# NanoRS485-MySens-v010-both-connectors.net
KiCad netlist of a schematic drawn in EAGLE
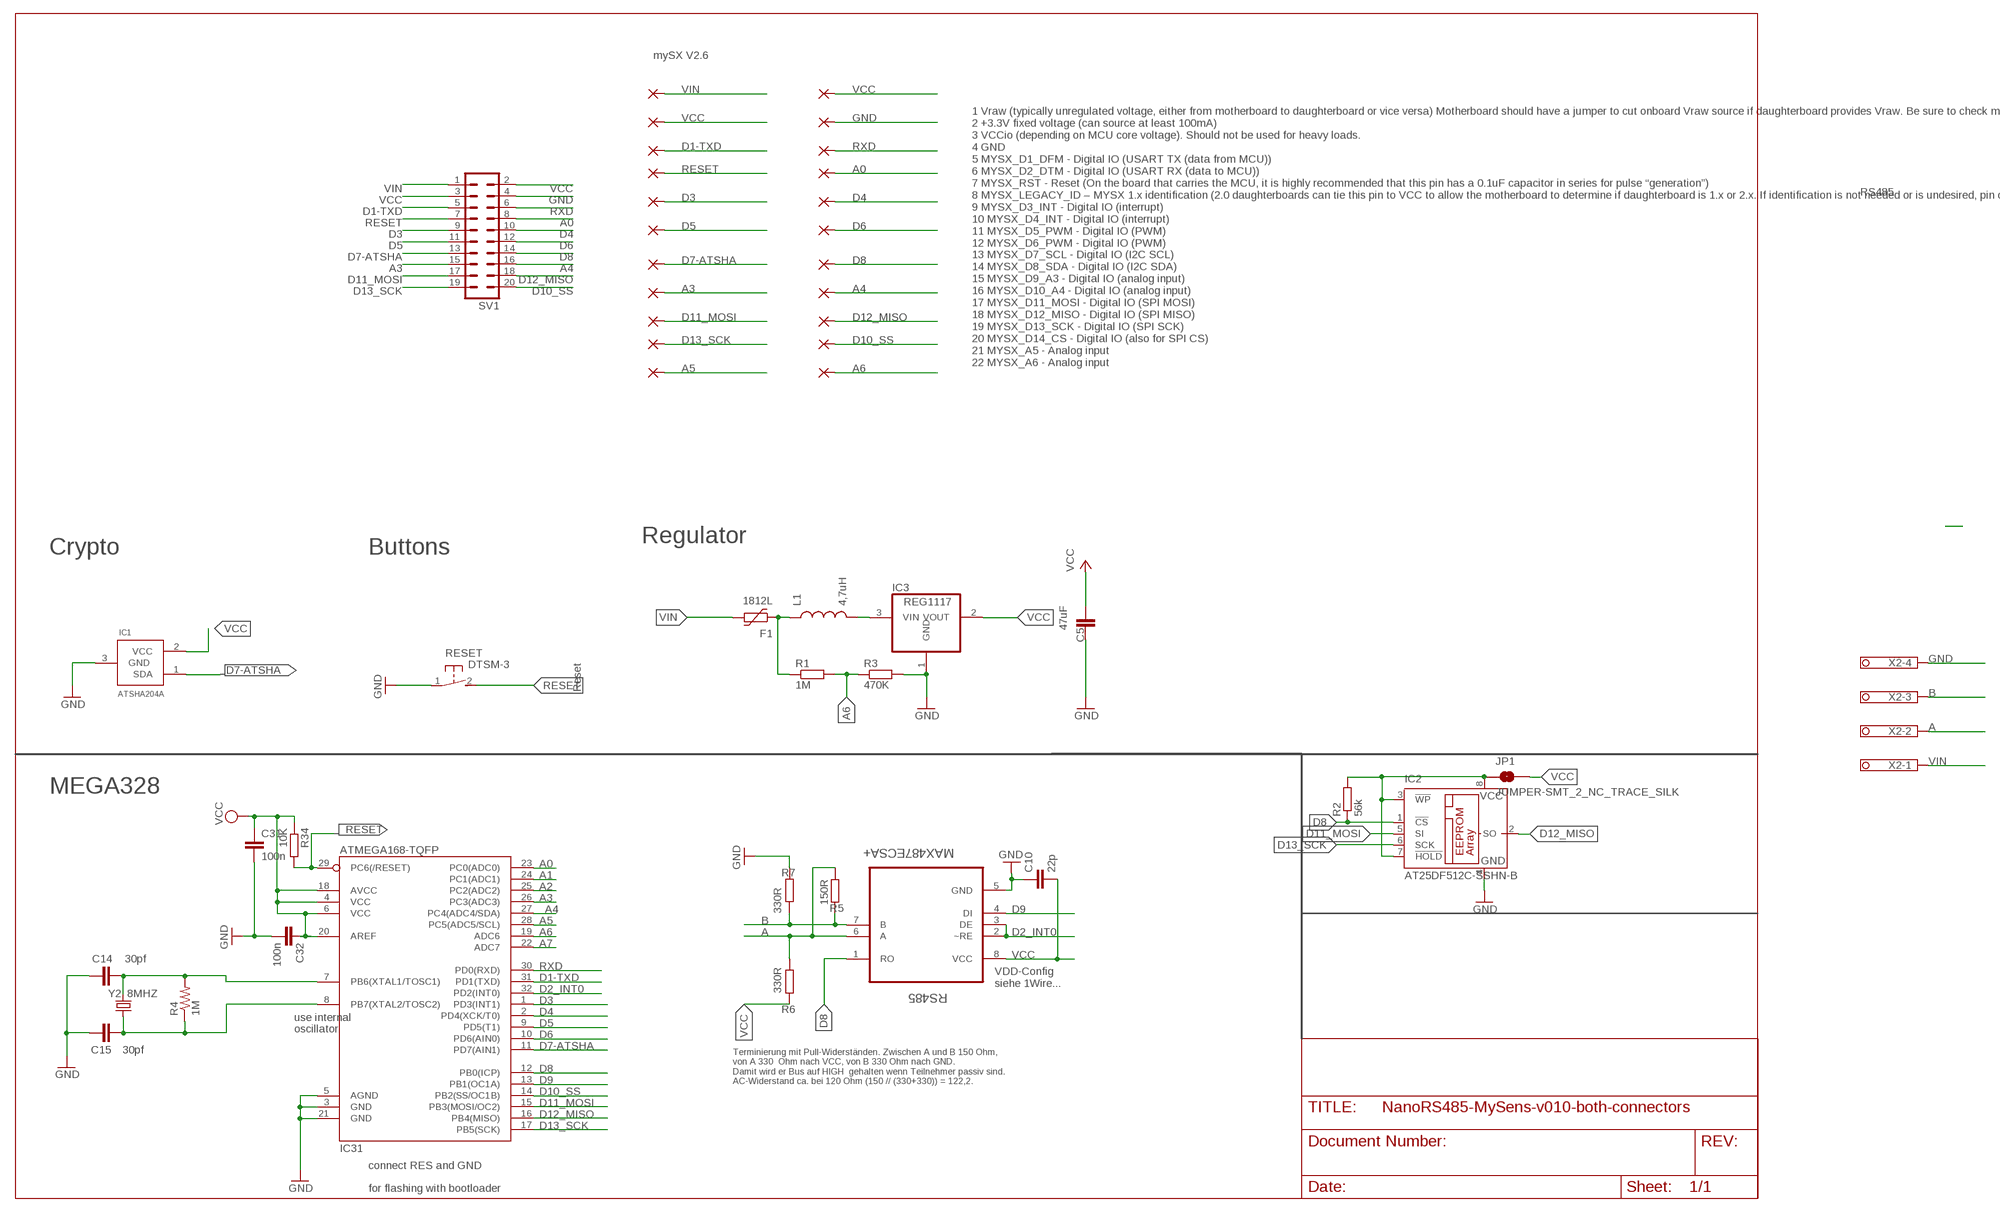
[diagram p0: schematic, sheet 1]

(export (version "E")
  (design (tool "Eeschema 10.0.6"))
  (components
    (comp (ref "3V3")
      (value "WIREPADSMD1,27-254")
      (footprint "eagle-import:SMD1,27-2,54")
      (libsource (lib "eagle-import") (part "WIREPADSMD1,27-254"))
    )
    (comp (ref "A3")
      (value "WIREPADSMD1,27-254")
      (footprint "eagle-import:SMD1,27-2,54")
      (libsource (lib "eagle-import") (part "WIREPADSMD1,27-254"))
    )
    (comp (ref "A4")
      (value "WIREPADSMD1,27-254")
      (footprint "eagle-import:SMD1,27-2,54")
      (libsource (lib "eagle-import") (part "WIREPADSMD1,27-254"))
    )
    (comp (ref "A5")
      (value "WIREPADSMD1,27-254")
      (footprint "eagle-import:SMD1,27-2,54")
      (libsource (lib "eagle-import") (part "WIREPADSMD1,27-254"))
    )
    (comp (ref "A6")
      (value "WIREPADSMD1,27-254")
      (footprint "eagle-import:SMD1,27-2,54")
      (libsource (lib "eagle-import") (part "WIREPADSMD1,27-254"))
    )
    (comp (ref "C5")
      (value "47uF")
      (footprint "eagle-import:C1210")
      (libsource (lib "eagle-import") (part "C-EUC1210"))
    )
    (comp (ref "C10")
      (value "22p")
      (footprint "eagle-import:C0805")
      (libsource (lib "eagle-import") (part "C-EUC0805"))
    )
    (comp (ref "C14")
      (value "30pf")
      (footprint "eagle-import:0805")
      (libsource (lib "eagle-import") (part "CAP0805"))
    )
    (comp (ref "C15")
      (value "30pf")
      (footprint "eagle-import:0805")
      (libsource (lib "eagle-import") (part "CAP0805"))
    )
    (comp (ref "C31")
      (value "100n")
      (footprint "eagle-import:C0805")
      (libsource (lib "eagle-import") (part "C-EUC0805"))
    )
    (comp (ref "C32")
      (value "100n")
      (footprint "eagle-import:C0805")
      (libsource (lib "eagle-import") (part "C-EUC0805"))
    )
    (comp (ref "D1")
      (value "WIREPADSMD1,27-254")
      (footprint "eagle-import:SMD1,27-2,54")
      (libsource (lib "eagle-import") (part "WIREPADSMD1,27-254"))
    )
    (comp (ref "D2")
      (value "WIREPADSMD1,27-254")
      (footprint "eagle-import:SMD1,27-2,54")
      (libsource (lib "eagle-import") (part "WIREPADSMD1,27-254"))
    )
    (comp (ref "D3")
      (value "WIREPADSMD1,27-254")
      (footprint "eagle-import:SMD1,27-2,54")
      (libsource (lib "eagle-import") (part "WIREPADSMD1,27-254"))
    )
    (comp (ref "D4")
      (value "WIREPADSMD1,27-254")
      (footprint "eagle-import:SMD1,27-2,54")
      (libsource (lib "eagle-import") (part "WIREPADSMD1,27-254"))
    )
    (comp (ref "D5")
      (value "WIREPADSMD1,27-254")
      (footprint "eagle-import:SMD1,27-2,54")
      (libsource (lib "eagle-import") (part "WIREPADSMD1,27-254"))
    )
    (comp (ref "D6")
      (value "WIREPADSMD1,27-254")
      (footprint "eagle-import:SMD1,27-2,54")
      (libsource (lib "eagle-import") (part "WIREPADSMD1,27-254"))
    )
    (comp (ref "D7")
      (value "WIREPADSMD1,27-254")
      (footprint "eagle-import:SMD1,27-2,54")
      (libsource (lib "eagle-import") (part "WIREPADSMD1,27-254"))
    )
    (comp (ref "D8")
      (value "WIREPADSMD1,27-254")
      (footprint "eagle-import:SMD1,27-2,54")
      (libsource (lib "eagle-import") (part "WIREPADSMD1,27-254"))
    )
    (comp (ref "D10-SS")
      (value "WIREPADSMD1,27-254")
      (footprint "eagle-import:SMD1,27-2,54")
      (libsource (lib "eagle-import") (part "WIREPADSMD1,27-254"))
    )
    (comp (ref "D11")
      (value "WIREPADSMD1,27-254")
      (footprint "eagle-import:SMD1,27-2,54")
      (libsource (lib "eagle-import") (part "WIREPADSMD1,27-254"))
    )
    (comp (ref "D12")
      (value "WIREPADSMD1,27-254")
      (footprint "eagle-import:SMD1,27-2,54")
      (libsource (lib "eagle-import") (part "WIREPADSMD1,27-254"))
    )
    (comp (ref "D13-SCK")
      (value "WIREPADSMD1,27-254")
      (footprint "eagle-import:SMD1,27-2,54")
      (libsource (lib "eagle-import") (part "WIREPADSMD1,27-254"))
    )
    (comp (ref "F1")
      (value "1812L")
      (footprint "eagle-import:1812L")
      (libsource (lib "eagle-import") (part "1812L"))
    )
    (comp (ref "GND")
      (value "WIREPADSMD1,27-254")
      (footprint "eagle-import:SMD1,27-2,54")
      (libsource (lib "eagle-import") (part "WIREPADSMD1,27-254"))
    )
    (comp (ref "IC1")
      (value "ATSHA204A")
      (footprint "eagle-import:SOT23")
      (libsource (lib "eagle-import") (part "ATSHA204A"))
    )
    (comp (ref "IC2")
      (value "AT25DF512C-SSHN-B")
      (footprint "eagle-import:SO-08")
      (fields (field (name "MF") "MICROCHIP") (field (name "MPN") "25AA080/SN"))
      (libsource (lib "eagle-import") (part "25SNAA080"))
    )
    (comp (ref "IC3")
      (value "REG1117")
      (footprint "eagle-import:SOT223")
      (libsource (lib "eagle-import") (part "REG1117"))
    )
    (comp (ref "IC31")
      (value "ATMEGA168-TQFP")
      (footprint "eagle-import:TQFP32-08")
      (libsource (lib "eagle-import") (part "ATMEGA168-TQFP"))
    )
    (comp (ref "JP1")
      (value "JUMPER-SMT_2_NC_TRACE_SILK")
      (footprint "eagle-import:SMT-JUMPER_2_NC_TRACE_SILK")
      (libsource (lib "eagle-import") (part "JUMPER-SMT_2_NC_TRACE_SILK"))
    )
    (comp (ref "L1")
      (value "4,7uH")
      (footprint "eagle-import:0805")
      (libsource (lib "eagle-import") (part "INDUCTOR0805"))
    )
    (comp (ref "R1")
      (value "1M")
      (footprint "eagle-import:R0805")
      (libsource (lib "eagle-import") (part "R-EU_R0805"))
    )
    (comp (ref "R2")
      (value "56k")
      (footprint "eagle-import:M0805")
      (libsource (lib "eagle-import") (part "resistor_R-EU_M0805"))
    )
    (comp (ref "R3")
      (value "470K")
      (footprint "eagle-import:R0805")
      (libsource (lib "eagle-import") (part "R-EU_R0805"))
    )
    (comp (ref "R4")
      (value "1M")
      (footprint "eagle-import:0805")
      (libsource (lib "eagle-import") (part "RESISTOR0805-RES"))
    )
    (comp (ref "R5")
      (value "150R")
      (footprint "eagle-import:R0805")
      (libsource (lib "eagle-import") (part "R-EU_R0805"))
    )
    (comp (ref "R6")
      (value "330R")
      (footprint "eagle-import:R0805")
      (libsource (lib "eagle-import") (part "R-EU_R0805"))
    )
    (comp (ref "R7")
      (value "330R")
      (footprint "eagle-import:R0805")
      (libsource (lib "eagle-import") (part "R-EU_R0805"))
    )
    (comp (ref "R34")
      (value "10K")
      (footprint "eagle-import:R0805")
      (libsource (lib "eagle-import") (part "R-EU_R0805"))
    )
    (comp (ref "RES")
      (value "WIREPADSMD1,27-254")
      (footprint "eagle-import:SMD1,27-2,54")
      (libsource (lib "eagle-import") (part "WIREPADSMD1,27-254"))
    )
    (comp (ref "RESET")
      (value "DTSM-3")
      (footprint "eagle-import:DTSM-3")
      (libsource (lib "eagle-import") (part "DTSM-3"))
    )
    (comp (ref "RS485")
      (value "MAX487ECSA+")
      (footprint "eagle-import:SOIC127P600X175-8N")
      (libsource (lib "eagle-import") (part "MAX487ECSA+"))
    )
    (comp (ref "SV1")
      (value "MA10-2")
      (footprint "eagle-import:MA10-2")
      (libsource (lib "eagle-import") (part "MA10-2"))
    )
    (comp (ref "VCC")
      (value "WIREPADSMD1,27-254")
      (footprint "eagle-import:SMD1,27-2,54")
      (libsource (lib "eagle-import") (part "WIREPADSMD1,27-254"))
    )
    (comp (ref "VCC-LEGACY")
      (value "WIREPADSMD1,27-254")
      (footprint "eagle-import:SMD1,27-2,54")
      (libsource (lib "eagle-import") (part "WIREPADSMD1,27-254"))
    )
    (comp (ref "VIN")
      (value "WIREPADSMD1,27-254")
      (footprint "eagle-import:SMD1,27-2,54")
      (libsource (lib "eagle-import") (part "WIREPADSMD1,27-254"))
    )
    (comp (ref "X2")
      (value "1751264")
      (footprint "eagle-import:1751264")
      (libsource (lib "eagle-import") (part "1751264"))
    )
    (comp (ref "Y2")
      (value "8MHZ")
      (footprint "eagle-import:CRYSTAL-TXC-7A")
      (libsource (lib "eagle-import") (part "CRYSTALTXC-7A"))
    )
  )
  (nets
    (net (code "1") (name "/A") (class "Default")
      (node (ref "R5") (pin "1") (pinfunction "1_1") (pintype "passive"))
      (node (ref "R6") (pin "2") (pinfunction "2_2") (pintype "passive"))
      (node (ref "RS485") (pin "6") (pinfunction "A_6") (pintype "bidirectional"))
      (node (ref "X2") (pin "2") (pinfunction "K_2") (pintype "passive"))
    )
    (net (code "2") (name "/A0") (class "Default")
      (node (ref "IC31") (pin "23") (pinfunction "PC0(ADC0)_23") (pintype "bidirectional"))
      (node (ref "SV1") (pin "8") (pinfunction "8_8") (pintype "passive"))
      (node (ref "VCC-LEGACY") (pin "1") (pinfunction "P_1") (pintype "passive"))
    )
    (net (code "3") (name "/A1") (class "Default")
      (node (ref "IC31") (pin "24") (pinfunction "PC1(ADC1)_24") (pintype "bidirectional"))
    )
    (net (code "4") (name "/A2") (class "Default")
      (node (ref "IC31") (pin "25") (pinfunction "PC2(ADC2)_25") (pintype "bidirectional"))
    )
    (net (code "5") (name "/A3") (class "Default")
      (node (ref "A3") (pin "1") (pinfunction "P_1") (pintype "passive"))
      (node (ref "IC31") (pin "26") (pinfunction "PC3(ADC3)_26") (pintype "bidirectional"))
      (node (ref "SV1") (pin "15") (pinfunction "15_15") (pintype "passive"))
    )
    (net (code "6") (name "/A4") (class "Default")
      (node (ref "A4") (pin "1") (pinfunction "P_1") (pintype "passive"))
      (node (ref "IC31") (pin "27") (pinfunction "PC4(ADC4/SDA)_27") (pintype "bidirectional"))
      (node (ref "SV1") (pin "16") (pinfunction "16_16") (pintype "passive"))
    )
    (net (code "7") (name "/A5") (class "Default")
      (node (ref "A5") (pin "1") (pinfunction "P_1") (pintype "passive"))
      (node (ref "IC31") (pin "28") (pinfunction "PC5(ADC5/SCL)_28") (pintype "bidirectional"))
    )
    (net (code "8") (name "/A7") (class "Default")
      (node (ref "IC31") (pin "22") (pinfunction "ADC7_22") (pintype "bidirectional"))
    )
    (net (code "9") (name "/B") (class "Default")
      (node (ref "R5") (pin "2") (pinfunction "2_2") (pintype "passive"))
      (node (ref "R7") (pin "1") (pinfunction "1_1") (pintype "passive"))
      (node (ref "RS485") (pin "7") (pinfunction "B_7") (pintype "bidirectional"))
      (node (ref "X2") (pin "3") (pinfunction "K_3") (pintype "passive"))
    )
    (net (code "10") (name "/D1-TXD") (class "Default")
      (node (ref "D1") (pin "1") (pinfunction "P_1") (pintype "passive"))
      (node (ref "IC31") (pin "31") (pinfunction "PD1(TXD)_31") (pintype "bidirectional"))
      (node (ref "SV1") (pin "5") (pinfunction "5_5") (pintype "passive"))
    )
    (net (code "11") (name "/D2_INT0") (class "Default")
      (node (ref "IC31") (pin "32") (pinfunction "PD2(INT0)_32") (pintype "bidirectional"))
      (node (ref "RS485") (pin "2") (pinfunction "~{RE}_2") (pintype "input"))
      (node (ref "RS485") (pin "3") (pinfunction "DE_3") (pintype "input"))
    )
    (net (code "12") (name "/D3") (class "Default")
      (node (ref "D3") (pin "1") (pinfunction "P_1") (pintype "passive"))
      (node (ref "IC31") (pin "1") (pinfunction "PD3(INT1)_1") (pintype "bidirectional"))
      (node (ref "SV1") (pin "9") (pinfunction "9_9") (pintype "passive"))
    )
    (net (code "13") (name "/D4") (class "Default")
      (node (ref "D4") (pin "1") (pinfunction "P_1") (pintype "passive"))
      (node (ref "IC31") (pin "2") (pinfunction "PD4(XCK/T0)_2") (pintype "bidirectional"))
      (node (ref "SV1") (pin "10") (pinfunction "10_10") (pintype "passive"))
    )
    (net (code "14") (name "/D5") (class "Default")
      (node (ref "D5") (pin "1") (pinfunction "P_1") (pintype "passive"))
      (node (ref "IC31") (pin "9") (pinfunction "PD5(T1)_9") (pintype "bidirectional"))
      (node (ref "SV1") (pin "11") (pinfunction "11_11") (pintype "passive"))
    )
    (net (code "15") (name "/D6") (class "Default")
      (node (ref "D6") (pin "1") (pinfunction "P_1") (pintype "passive"))
      (node (ref "IC31") (pin "10") (pinfunction "PD6(AIN0)_10") (pintype "bidirectional"))
      (node (ref "SV1") (pin "12") (pinfunction "12_12") (pintype "passive"))
    )
    (net (code "16") (name "/D7-ATSHA") (class "Default")
      (node (ref "D7") (pin "1") (pinfunction "P_1") (pintype "passive"))
      (node (ref "IC1") (pin "1") (pinfunction "SDA_1") (pintype "bidirectional"))
      (node (ref "IC31") (pin "11") (pinfunction "PD7(AIN1)_11") (pintype "bidirectional"))
      (node (ref "SV1") (pin "13") (pinfunction "13_13") (pintype "passive"))
    )
    (net (code "17") (name "/D9") (class "Default")
      (node (ref "IC31") (pin "13") (pinfunction "PB1(OC1A)_13") (pintype "bidirectional"))
      (node (ref "RS485") (pin "4") (pinfunction "DI_4") (pintype "input"))
    )
    (net (code "18") (name "/D10_SS") (class "Default")
      (node (ref "D10-SS") (pin "1") (pinfunction "P_1") (pintype "passive"))
      (node (ref "IC31") (pin "14") (pinfunction "PB2(SS/OC1B)_14") (pintype "bidirectional"))
      (node (ref "SV1") (pin "20") (pinfunction "20_20") (pintype "passive"))
    )
    (net (code "19") (name "/RXD") (class "Default")
      (node (ref "D2") (pin "1") (pinfunction "P_1") (pintype "passive"))
      (node (ref "IC31") (pin "30") (pinfunction "PD0(RXD)_30") (pintype "bidirectional"))
      (node (ref "SV1") (pin "6") (pinfunction "6_6") (pintype "passive"))
    )
    (net (code "20") (name "A6") (class "Default")
      (node (ref "A6") (pin "1") (pinfunction "P_1") (pintype "passive"))
      (node (ref "IC31") (pin "19") (pinfunction "ADC6_19") (pintype "bidirectional"))
      (node (ref "R1") (pin "2") (pinfunction "2_2") (pintype "passive"))
      (node (ref "R3") (pin "1") (pinfunction "1_1") (pintype "passive"))
    )
    (net (code "21") (name "D8") (class "Default")
      (node (ref "D8") (pin "1") (pinfunction "P_1") (pintype "passive"))
      (node (ref "IC2") (pin "1") (pinfunction "~{CS}_1") (pintype "input"))
      (node (ref "IC31") (pin "12") (pinfunction "PB0(ICP)_12") (pintype "bidirectional"))
      (node (ref "R2") (pin "1") (pinfunction "1_1") (pintype "passive"))
      (node (ref "RS485") (pin "1") (pinfunction "RO_1") (pintype "output"))
      (node (ref "SV1") (pin "14") (pinfunction "14_14") (pintype "passive"))
    )
    (net (code "22") (name "D11_MOSI") (class "Default")
      (node (ref "D11") (pin "1") (pinfunction "P_1") (pintype "passive"))
      (node (ref "IC2") (pin "5") (pinfunction "SI_5") (pintype "input"))
      (node (ref "IC31") (pin "15") (pinfunction "PB3(MOSI/OC2)_15") (pintype "bidirectional"))
      (node (ref "SV1") (pin "17") (pinfunction "17_17") (pintype "passive"))
    )
    (net (code "23") (name "D12_MISO") (class "Default")
      (node (ref "D12") (pin "1") (pinfunction "P_1") (pintype "passive"))
      (node (ref "IC2") (pin "2") (pinfunction "SO_2") (pintype "bidirectional"))
      (node (ref "IC31") (pin "16") (pinfunction "PB4(MISO)_16") (pintype "bidirectional"))
      (node (ref "SV1") (pin "18") (pinfunction "18_18") (pintype "passive"))
    )
    (net (code "24") (name "D13_SCK") (class "Default")
      (node (ref "D13-SCK") (pin "1") (pinfunction "P_1") (pintype "passive"))
      (node (ref "IC2") (pin "6") (pinfunction "SCK_6") (pintype "input"))
      (node (ref "IC31") (pin "17") (pinfunction "PB5(SCK)_17") (pintype "bidirectional"))
      (node (ref "SV1") (pin "19") (pinfunction "19_19") (pintype "passive"))
    )
    (net (code "25") (name "GND") (class "Default")
      (node (ref "C10") (pin "1") (pinfunction "1_1") (pintype "passive"))
      (node (ref "C14") (pin "1") (pinfunction "1_1") (pintype "passive"))
      (node (ref "C15") (pin "1") (pinfunction "1_1") (pintype "passive"))
      (node (ref "C31") (pin "2") (pinfunction "2_2") (pintype "passive"))
      (node (ref "C32") (pin "2") (pinfunction "2_2") (pintype "passive"))
      (node (ref "C5") (pin "1") (pinfunction "1_1") (pintype "passive"))
      (node (ref "GND") (pin "1") (pinfunction "P_1") (pintype "passive"))
      (node (ref "IC1") (pin "3") (pinfunction "GND_3") (pintype "bidirectional"))
      (node (ref "IC2") (pin "4") (pinfunction "GND_4") (pintype "power_in"))
      (node (ref "IC3") (pin "1") (pinfunction "GND_1") (pintype "power_in"))
      (node (ref "IC31") (pin "21") (pinfunction "GND_21") (pintype "bidirectional"))
      (node (ref "IC31") (pin "3") (pinfunction "GND_3") (pintype "bidirectional"))
      (node (ref "IC31") (pin "5") (pinfunction "AGND_5") (pintype "bidirectional"))
      (node (ref "R3") (pin "2") (pinfunction "2_2") (pintype "passive"))
      (node (ref "R7") (pin "2") (pinfunction "2_2") (pintype "passive"))
      (node (ref "RESET") (pin "1") (pinfunction "1_1") (pintype "passive"))
      (node (ref "RS485") (pin "5") (pinfunction "GND_5") (pintype "passive"))
      (node (ref "SV1") (pin "4") (pinfunction "4_4") (pintype "passive"))
      (node (ref "X2") (pin "4") (pinfunction "K_4") (pintype "passive"))
    )
    (net (code "26") (name "Net-(F1-1)") (class "Default")
      (node (ref "F1") (pin "P$1") (pinfunction "1_P$1") (pintype "passive"))
      (node (ref "L1") (pin "1") (pinfunction "1_1") (pintype "passive"))
      (node (ref "R1") (pin "1") (pinfunction "1_1") (pintype "passive"))
    )
    (net (code "27") (name "Net-(IC2-VCC)") (class "Default")
      (node (ref "IC2") (pin "3") (pinfunction "~{WP}_3") (pintype "input"))
      (node (ref "IC2") (pin "7") (pinfunction "~{HOLD}_7") (pintype "input"))
      (node (ref "IC2") (pin "8") (pinfunction "VCC_8") (pintype "power_in"))
      (node (ref "JP1") (pin "1") (pinfunction "1_1") (pintype "passive"))
      (node (ref "R2") (pin "2") (pinfunction "2_2") (pintype "passive"))
    )
    (net (code "28") (name "Net-(IC3-VIN)") (class "Default")
      (node (ref "IC3") (pin "3") (pinfunction "VIN_3") (pintype "input"))
      (node (ref "L1") (pin "2") (pinfunction "2_2") (pintype "passive"))
    )
    (net (code "29") (name "Net-(IC31-PB6(XTAL1{slash}TOSC1))") (class "Default")
      (node (ref "C14") (pin "2") (pinfunction "2_2") (pintype "passive"))
      (node (ref "IC31") (pin "7") (pinfunction "PB6(XTAL1/TOSC1)_7") (pintype "bidirectional"))
      (node (ref "R4") (pin "2") (pinfunction "2_2") (pintype "passive"))
      (node (ref "Y2") (pin "P$2") (pinfunction "2_P$2") (pintype "passive"))
    )
    (net (code "30") (name "Net-(IC31-PB7(XTAL2{slash}TOSC2))") (class "Default")
      (node (ref "C15") (pin "2") (pinfunction "2_2") (pintype "passive"))
      (node (ref "IC31") (pin "8") (pinfunction "PB7(XTAL2/TOSC2)_8") (pintype "bidirectional"))
      (node (ref "R4") (pin "1") (pinfunction "1_1") (pintype "passive"))
      (node (ref "Y2") (pin "P$1") (pinfunction "1_P$1") (pintype "passive"))
    )
    (net (code "31") (name "RESET") (class "Default")
      (node (ref "IC31") (pin "29") (pinfunction "PC6(/RESET)_29") (pintype "bidirectional"))
      (node (ref "R34") (pin "2") (pinfunction "2_2") (pintype "passive"))
      (node (ref "RES") (pin "1") (pinfunction "P_1") (pintype "passive"))
      (node (ref "RESET") (pin "2") (pinfunction "2_2") (pintype "passive"))
      (node (ref "SV1") (pin "7") (pinfunction "7_7") (pintype "passive"))
    )
    (net (code "32") (name "VCC") (class "Default")
      (node (ref "3V3") (pin "1") (pinfunction "P_1") (pintype "passive"))
      (node (ref "C10") (pin "2") (pinfunction "2_2") (pintype "passive"))
      (node (ref "C31") (pin "1") (pinfunction "1_1") (pintype "passive"))
      (node (ref "C32") (pin "1") (pinfunction "1_1") (pintype "passive"))
      (node (ref "C5") (pin "2") (pinfunction "2_2") (pintype "passive"))
      (node (ref "IC1") (pin "2") (pinfunction "VCC_2") (pintype "bidirectional"))
      (node (ref "IC3") (pin "2") (pinfunction "VOUT_2") (pintype "output"))
      (node (ref "IC31") (pin "18") (pinfunction "AVCC_18") (pintype "bidirectional"))
      (node (ref "IC31") (pin "20") (pinfunction "AREF_20") (pintype "bidirectional"))
      (node (ref "IC31") (pin "4") (pinfunction "VCC_4") (pintype "bidirectional"))
      (node (ref "IC31") (pin "6") (pinfunction "VCC_6") (pintype "bidirectional"))
      (node (ref "JP1") (pin "2") (pinfunction "2_2") (pintype "passive"))
      (node (ref "R34") (pin "1") (pinfunction "1_1") (pintype "passive"))
      (node (ref "R6") (pin "1") (pinfunction "1_1") (pintype "passive"))
      (node (ref "RS485") (pin "8") (pinfunction "VCC_8") (pintype "power_in"))
      (node (ref "SV1") (pin "2") (pinfunction "2_2") (pintype "passive"))
      (node (ref "SV1") (pin "3") (pinfunction "3_3") (pintype "passive"))
      (node (ref "VCC") (pin "1") (pinfunction "P_1") (pintype "passive"))
    )
    (net (code "33") (name "VIN") (class "Default")
      (node (ref "F1") (pin "P$2") (pinfunction "2_P$2") (pintype "passive"))
      (node (ref "SV1") (pin "1") (pinfunction "1_1") (pintype "passive"))
      (node (ref "VIN") (pin "1") (pinfunction "P_1") (pintype "passive"))
      (node (ref "X2") (pin "1") (pinfunction "K_1") (pintype "passive"))
    )
  )
)
